# Lamp_C_Unit.net
KiCad netlist of a schematic drawn in Altium Designer
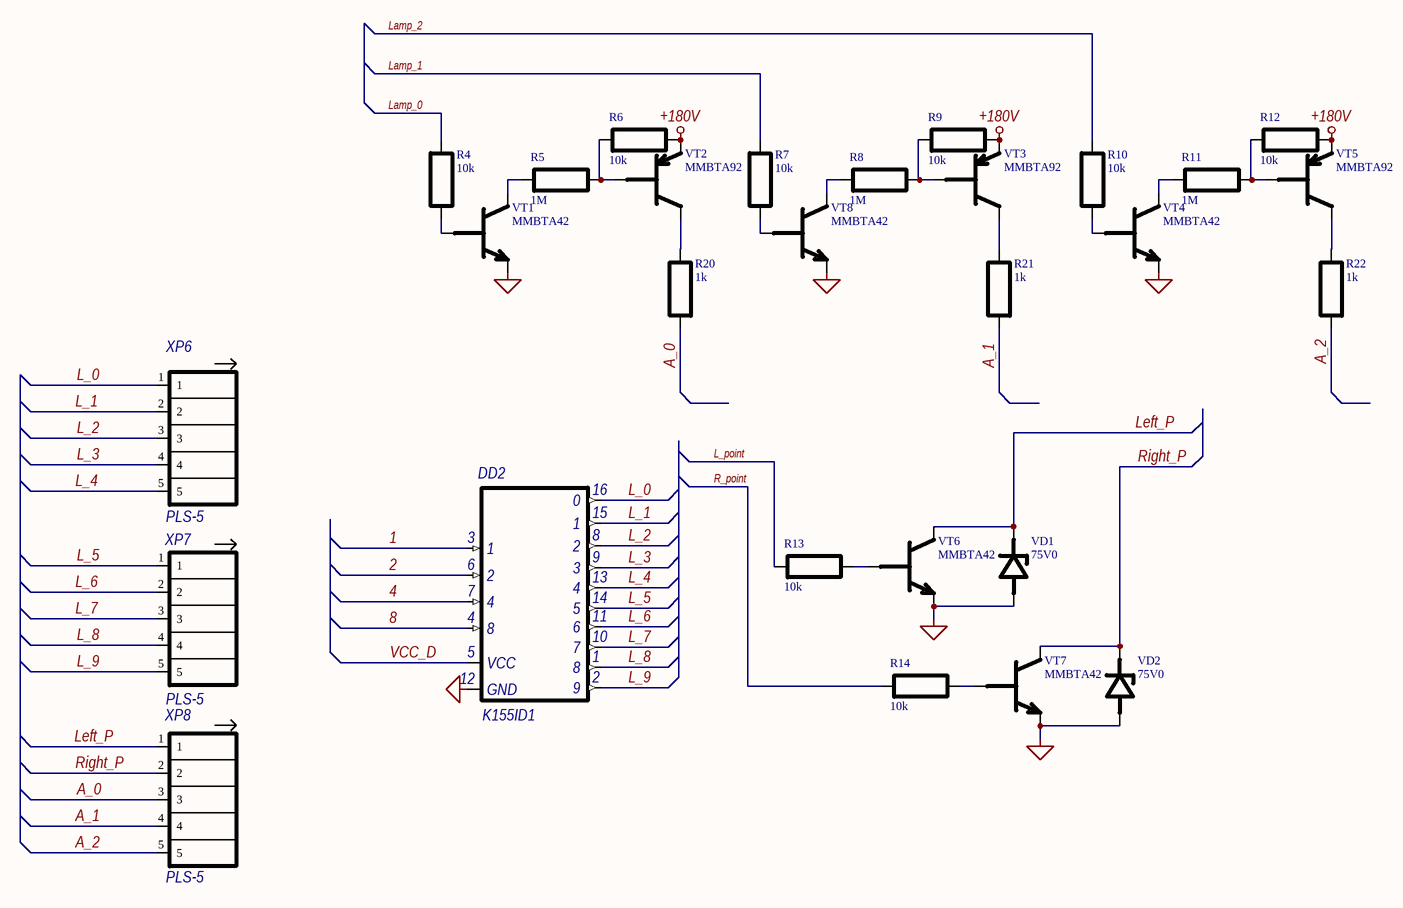
[diagram p0: Lamp_C_Unit.SchDoc]

(export (version "E")
  (design (tool "Eeschema 10.0.6"))
  (components
    (comp (ref "DD2") (value "K155ID1") (footprint "DIP16") (libsource (lib "sobol_lib") (part "K155ID1")))
    (comp (ref "R4")
      (value "10k")
      (footprint "CR2012-0805")
      (libsource (lib "sobol_lib") (part "R0805-10k-5%"))
    )
    (comp (ref "R5")
      (value "1M")
      (footprint "CR2012-0805")
      (libsource (lib "sobol_lib") (part "R0805-10k-5%"))
    )
    (comp (ref "R6")
      (value "10k")
      (footprint "CR2012-0805")
      (libsource (lib "sobol_lib") (part "R0805-10k-5%"))
    )
    (comp (ref "R7")
      (value "10k")
      (footprint "CR2012-0805")
      (libsource (lib "sobol_lib") (part "R0805-10k-5%"))
    )
    (comp (ref "R8")
      (value "1M")
      (footprint "CR2012-0805")
      (libsource (lib "sobol_lib") (part "R0805-10k-5%"))
    )
    (comp (ref "R9")
      (value "10k")
      (footprint "CR2012-0805")
      (libsource (lib "sobol_lib") (part "R0805-10k-5%"))
    )
    (comp (ref "R10")
      (value "10k")
      (footprint "CR2012-0805")
      (libsource (lib "sobol_lib") (part "R0805-10k-5%"))
    )
    (comp (ref "R11")
      (value "1M")
      (footprint "CR2012-0805")
      (libsource (lib "sobol_lib") (part "R0805-10k-5%"))
    )
    (comp (ref "R12")
      (value "10k")
      (footprint "CR2012-0805")
      (libsource (lib "sobol_lib") (part "R0805-10k-5%"))
    )
    (comp (ref "R13")
      (value "10k")
      (footprint "CR2012-0805")
      (libsource (lib "sobol_lib") (part "R0805-10k-5%"))
    )
    (comp (ref "R14")
      (value "10k")
      (footprint "CR2012-0805")
      (libsource (lib "sobol_lib") (part "R0805-10k-5%"))
    )
    (comp (ref "R20")
      (value "1k")
      (footprint "CR2012-0805")
      (libsource (lib "sobol_lib") (part "R0805-1k-5%"))
    )
    (comp (ref "R21")
      (value "1k")
      (footprint "CR2012-0805")
      (libsource (lib "sobol_lib") (part "R0805-1k-5%"))
    )
    (comp (ref "R22")
      (value "1k")
      (footprint "CR2012-0805")
      (libsource (lib "sobol_lib") (part "R0805-1k-5%"))
    )
    (comp (ref "VD1") (value "75V0") (footprint "SOD-80") (libsource (lib "sobol_lib") (part "BZV55-C20V0")))
    (comp (ref "VD2") (value "75V0") (footprint "SOD-80") (libsource (lib "sobol_lib") (part "BZV55-C20V0")))
    (comp (ref "VT1") (value "MMBTA42") (footprint "SOT-23") (libsource (lib "sobol_lib") (part "MMBTA42")))
    (comp (ref "VT2") (value "MMBTA92") (footprint "SOT-23") (libsource (lib "sobol_lib") (part "MMBTA92")))
    (comp (ref "VT3") (value "MMBTA92") (footprint "SOT-23") (libsource (lib "sobol_lib") (part "MMBTA92")))
    (comp (ref "VT4") (value "MMBTA42") (footprint "SOT-23") (libsource (lib "sobol_lib") (part "MMBTA42")))
    (comp (ref "VT5") (value "MMBTA92") (footprint "SOT-23") (libsource (lib "sobol_lib") (part "MMBTA92")))
    (comp (ref "VT6") (value "MMBTA42") (footprint "SOT-23") (libsource (lib "sobol_lib") (part "MMBTA42")))
    (comp (ref "VT7") (value "MMBTA42") (footprint "SOT-23") (libsource (lib "sobol_lib") (part "MMBTA42")))
    (comp (ref "VT8") (value "MMBTA42") (footprint "SOT-23") (libsource (lib "sobol_lib") (part "MMBTA42")))
    (comp (ref "XP6") (value "PLS-5") (footprint "PLS-5") (libsource (lib "sobol_lib") (part "PLS-5")))
    (comp (ref "XP7") (value "PLS-5") (footprint "PLS-5") (libsource (lib "sobol_lib") (part "PLS-5")))
    (comp (ref "XP8") (value "PLS-5") (footprint "PLS-5") (libsource (lib "sobol_lib") (part "PLS-5")))
  )
  (nets
    (net (code "1") (name "+180V") (class "Default")
      (node (ref "R12") (pin "2") (pinfunction "2_2") (pintype "passive"))
      (node (ref "R6") (pin "2") (pinfunction "2_2") (pintype "passive"))
      (node (ref "R9") (pin "2") (pinfunction "2_2") (pintype "passive"))
      (node (ref "VT2") (pin "2") (pinfunction "E_2") (pintype "passive"))
      (node (ref "VT3") (pin "2") (pinfunction "E_2") (pintype "passive"))
      (node (ref "VT5") (pin "2") (pinfunction "E_2") (pintype "passive"))
    )
    (net (code "2") (name "/1") (class "Default")
      (node (ref "DD2") (pin "3") (pinfunction "1_3") (pintype "input"))
    )
    (net (code "3") (name "/2") (class "Default")
      (node (ref "DD2") (pin "6") (pinfunction "2_6") (pintype "input"))
    )
    (net (code "4") (name "/4") (class "Default")
      (node (ref "DD2") (pin "7") (pinfunction "4_7") (pintype "input"))
    )
    (net (code "5") (name "/8") (class "Default")
      (node (ref "DD2") (pin "4") (pinfunction "8_4") (pintype "input"))
    )
    (net (code "6") (name "/A_0") (class "Default")
      (node (ref "R20") (pin "1") (pinfunction "1_1") (pintype "passive"))
      (node (ref "XP8") (pin "3") (pinfunction "3_3") (pintype "passive"))
    )
    (net (code "7") (name "/A_1") (class "Default")
      (node (ref "R21") (pin "1") (pinfunction "1_1") (pintype "passive"))
      (node (ref "XP8") (pin "4") (pinfunction "4_4") (pintype "passive"))
    )
    (net (code "8") (name "/A_2") (class "Default")
      (node (ref "R22") (pin "1") (pinfunction "1_1") (pintype "passive"))
      (node (ref "XP8") (pin "5") (pinfunction "5_5") (pintype "passive"))
    )
    (net (code "9") (name "/L_0") (class "Default")
      (node (ref "DD2") (pin "16") (pinfunction "0_16") (pintype "output"))
      (node (ref "XP6") (pin "1") (pinfunction "1_1") (pintype "passive"))
    )
    (net (code "10") (name "/L_1") (class "Default")
      (node (ref "DD2") (pin "15") (pinfunction "1_15") (pintype "output"))
      (node (ref "XP6") (pin "2") (pinfunction "2_2") (pintype "passive"))
    )
    (net (code "11") (name "/L_2") (class "Default")
      (node (ref "DD2") (pin "8") (pinfunction "2_8") (pintype "output"))
      (node (ref "XP6") (pin "3") (pinfunction "3_3") (pintype "passive"))
    )
    (net (code "12") (name "/L_3") (class "Default")
      (node (ref "DD2") (pin "9") (pinfunction "3_9") (pintype "output"))
      (node (ref "XP6") (pin "4") (pinfunction "4_4") (pintype "passive"))
    )
    (net (code "13") (name "/L_4") (class "Default")
      (node (ref "DD2") (pin "13") (pinfunction "4_13") (pintype "output"))
      (node (ref "XP6") (pin "5") (pinfunction "5_5") (pintype "passive"))
    )
    (net (code "14") (name "/L_5") (class "Default")
      (node (ref "DD2") (pin "14") (pinfunction "5_14") (pintype "output"))
      (node (ref "XP7") (pin "1") (pinfunction "1_1") (pintype "passive"))
    )
    (net (code "15") (name "/L_6") (class "Default")
      (node (ref "DD2") (pin "11") (pinfunction "6_11") (pintype "output"))
      (node (ref "XP7") (pin "2") (pinfunction "2_2") (pintype "passive"))
    )
    (net (code "16") (name "/L_7") (class "Default")
      (node (ref "DD2") (pin "10") (pinfunction "7_10") (pintype "output"))
      (node (ref "XP7") (pin "3") (pinfunction "3_3") (pintype "passive"))
    )
    (net (code "17") (name "/L_8") (class "Default")
      (node (ref "DD2") (pin "1") (pinfunction "8_1") (pintype "output"))
      (node (ref "XP7") (pin "4") (pinfunction "4_4") (pintype "passive"))
    )
    (net (code "18") (name "/L_9") (class "Default")
      (node (ref "DD2") (pin "2") (pinfunction "9_2") (pintype "output"))
      (node (ref "XP7") (pin "5") (pinfunction "5_5") (pintype "passive"))
    )
    (net (code "19") (name "/L_point") (class "Default")
      (node (ref "R13") (pin "1") (pinfunction "1_1") (pintype "passive"))
    )
    (net (code "20") (name "/Lamp_0") (class "Default")
      (node (ref "R4") (pin "1") (pinfunction "1_1") (pintype "passive"))
    )
    (net (code "21") (name "/Lamp_1") (class "Default")
      (node (ref "R7") (pin "1") (pinfunction "1_1") (pintype "passive"))
    )
    (net (code "22") (name "/Lamp_2") (class "Default")
      (node (ref "R10") (pin "1") (pinfunction "1_1") (pintype "passive"))
    )
    (net (code "23") (name "/Left_P") (class "Default")
      (node (ref "VD1") (pin "2") (pinfunction "K_2") (pintype "passive"))
      (node (ref "VT6") (pin "3") (pinfunction "C_3") (pintype "passive"))
      (node (ref "XP8") (pin "1") (pinfunction "1_1") (pintype "passive"))
    )
    (net (code "24") (name "/R_point") (class "Default")
      (node (ref "R14") (pin "1") (pinfunction "1_1") (pintype "passive"))
    )
    (net (code "25") (name "/Right_P") (class "Default")
      (node (ref "VD2") (pin "2") (pinfunction "K_2") (pintype "passive"))
      (node (ref "VT7") (pin "3") (pinfunction "C_3") (pintype "passive"))
      (node (ref "XP8") (pin "2") (pinfunction "2_2") (pintype "passive"))
    )
    (net (code "26") (name "/VCC_D") (class "Default")
      (node (ref "DD2") (pin "5") (pinfunction "VCC_5") (pintype "power_in"))
    )
    (net (code "27") (name "Net-(VT1-B)") (class "Default")
      (node (ref "R4") (pin "2") (pinfunction "2_2") (pintype "passive"))
      (node (ref "VT1") (pin "1") (pinfunction "B_1") (pintype "passive"))
    )
    (net (code "28") (name "Net-(VT1-C)") (class "Default")
      (node (ref "R5") (pin "1") (pinfunction "1_1") (pintype "passive"))
      (node (ref "VT1") (pin "3") (pinfunction "C_3") (pintype "passive"))
    )
    (net (code "29") (name "Net-(VT2-B)") (class "Default")
      (node (ref "R5") (pin "2") (pinfunction "2_2") (pintype "passive"))
      (node (ref "R6") (pin "1") (pinfunction "1_1") (pintype "passive"))
      (node (ref "VT2") (pin "1") (pinfunction "B_1") (pintype "passive"))
    )
    (net (code "30") (name "Net-(VT2-C)") (class "Default")
      (node (ref "R20") (pin "2") (pinfunction "2_2") (pintype "passive"))
      (node (ref "VT2") (pin "3") (pinfunction "C_3") (pintype "passive"))
    )
    (net (code "31") (name "Net-(VT3-B)") (class "Default")
      (node (ref "R8") (pin "2") (pinfunction "2_2") (pintype "passive"))
      (node (ref "R9") (pin "1") (pinfunction "1_1") (pintype "passive"))
      (node (ref "VT3") (pin "1") (pinfunction "B_1") (pintype "passive"))
    )
    (net (code "32") (name "Net-(VT3-C)") (class "Default")
      (node (ref "R21") (pin "2") (pinfunction "2_2") (pintype "passive"))
      (node (ref "VT3") (pin "3") (pinfunction "C_3") (pintype "passive"))
    )
    (net (code "33") (name "Net-(VT4-B)") (class "Default")
      (node (ref "R10") (pin "2") (pinfunction "2_2") (pintype "passive"))
      (node (ref "VT4") (pin "1") (pinfunction "B_1") (pintype "passive"))
    )
    (net (code "34") (name "Net-(VT4-C)") (class "Default")
      (node (ref "R11") (pin "1") (pinfunction "1_1") (pintype "passive"))
      (node (ref "VT4") (pin "3") (pinfunction "C_3") (pintype "passive"))
    )
    (net (code "35") (name "Net-(VT5-B)") (class "Default")
      (node (ref "R11") (pin "2") (pinfunction "2_2") (pintype "passive"))
      (node (ref "R12") (pin "1") (pinfunction "1_1") (pintype "passive"))
      (node (ref "VT5") (pin "1") (pinfunction "B_1") (pintype "passive"))
    )
    (net (code "36") (name "Net-(VT5-C)") (class "Default")
      (node (ref "R22") (pin "2") (pinfunction "2_2") (pintype "passive"))
      (node (ref "VT5") (pin "3") (pinfunction "C_3") (pintype "passive"))
    )
    (net (code "37") (name "Net-(VT6-B)") (class "Default")
      (node (ref "R13") (pin "2") (pinfunction "2_2") (pintype "passive"))
      (node (ref "VT6") (pin "1") (pinfunction "B_1") (pintype "passive"))
    )
    (net (code "38") (name "Net-(VT7-B)") (class "Default")
      (node (ref "R14") (pin "2") (pinfunction "2_2") (pintype "passive"))
      (node (ref "VT7") (pin "1") (pinfunction "B_1") (pintype "passive"))
    )
    (net (code "39") (name "Net-(VT8-B)") (class "Default")
      (node (ref "R7") (pin "2") (pinfunction "2_2") (pintype "passive"))
      (node (ref "VT8") (pin "1") (pinfunction "B_1") (pintype "passive"))
    )
    (net (code "40") (name "Net-(VT8-C)") (class "Default")
      (node (ref "R8") (pin "1") (pinfunction "1_1") (pintype "passive"))
      (node (ref "VT8") (pin "3") (pinfunction "C_3") (pintype "passive"))
    )
    (net (code "41") (name "SGND") (class "Default")
      (node (ref "DD2") (pin "12") (pinfunction "GND_12") (pintype "power_in"))
      (node (ref "VD1") (pin "1") (pinfunction "A_1") (pintype "passive"))
      (node (ref "VD2") (pin "1") (pinfunction "A_1") (pintype "passive"))
      (node (ref "VT1") (pin "2") (pinfunction "E_2") (pintype "passive"))
      (node (ref "VT4") (pin "2") (pinfunction "E_2") (pintype "passive"))
      (node (ref "VT6") (pin "2") (pinfunction "E_2") (pintype "passive"))
      (node (ref "VT7") (pin "2") (pinfunction "E_2") (pintype "passive"))
      (node (ref "VT8") (pin "2") (pinfunction "E_2") (pintype "passive"))
    )
  )
)
